# Croduino_Nova.net
KiCad netlist of a schematic drawn in EAGLE
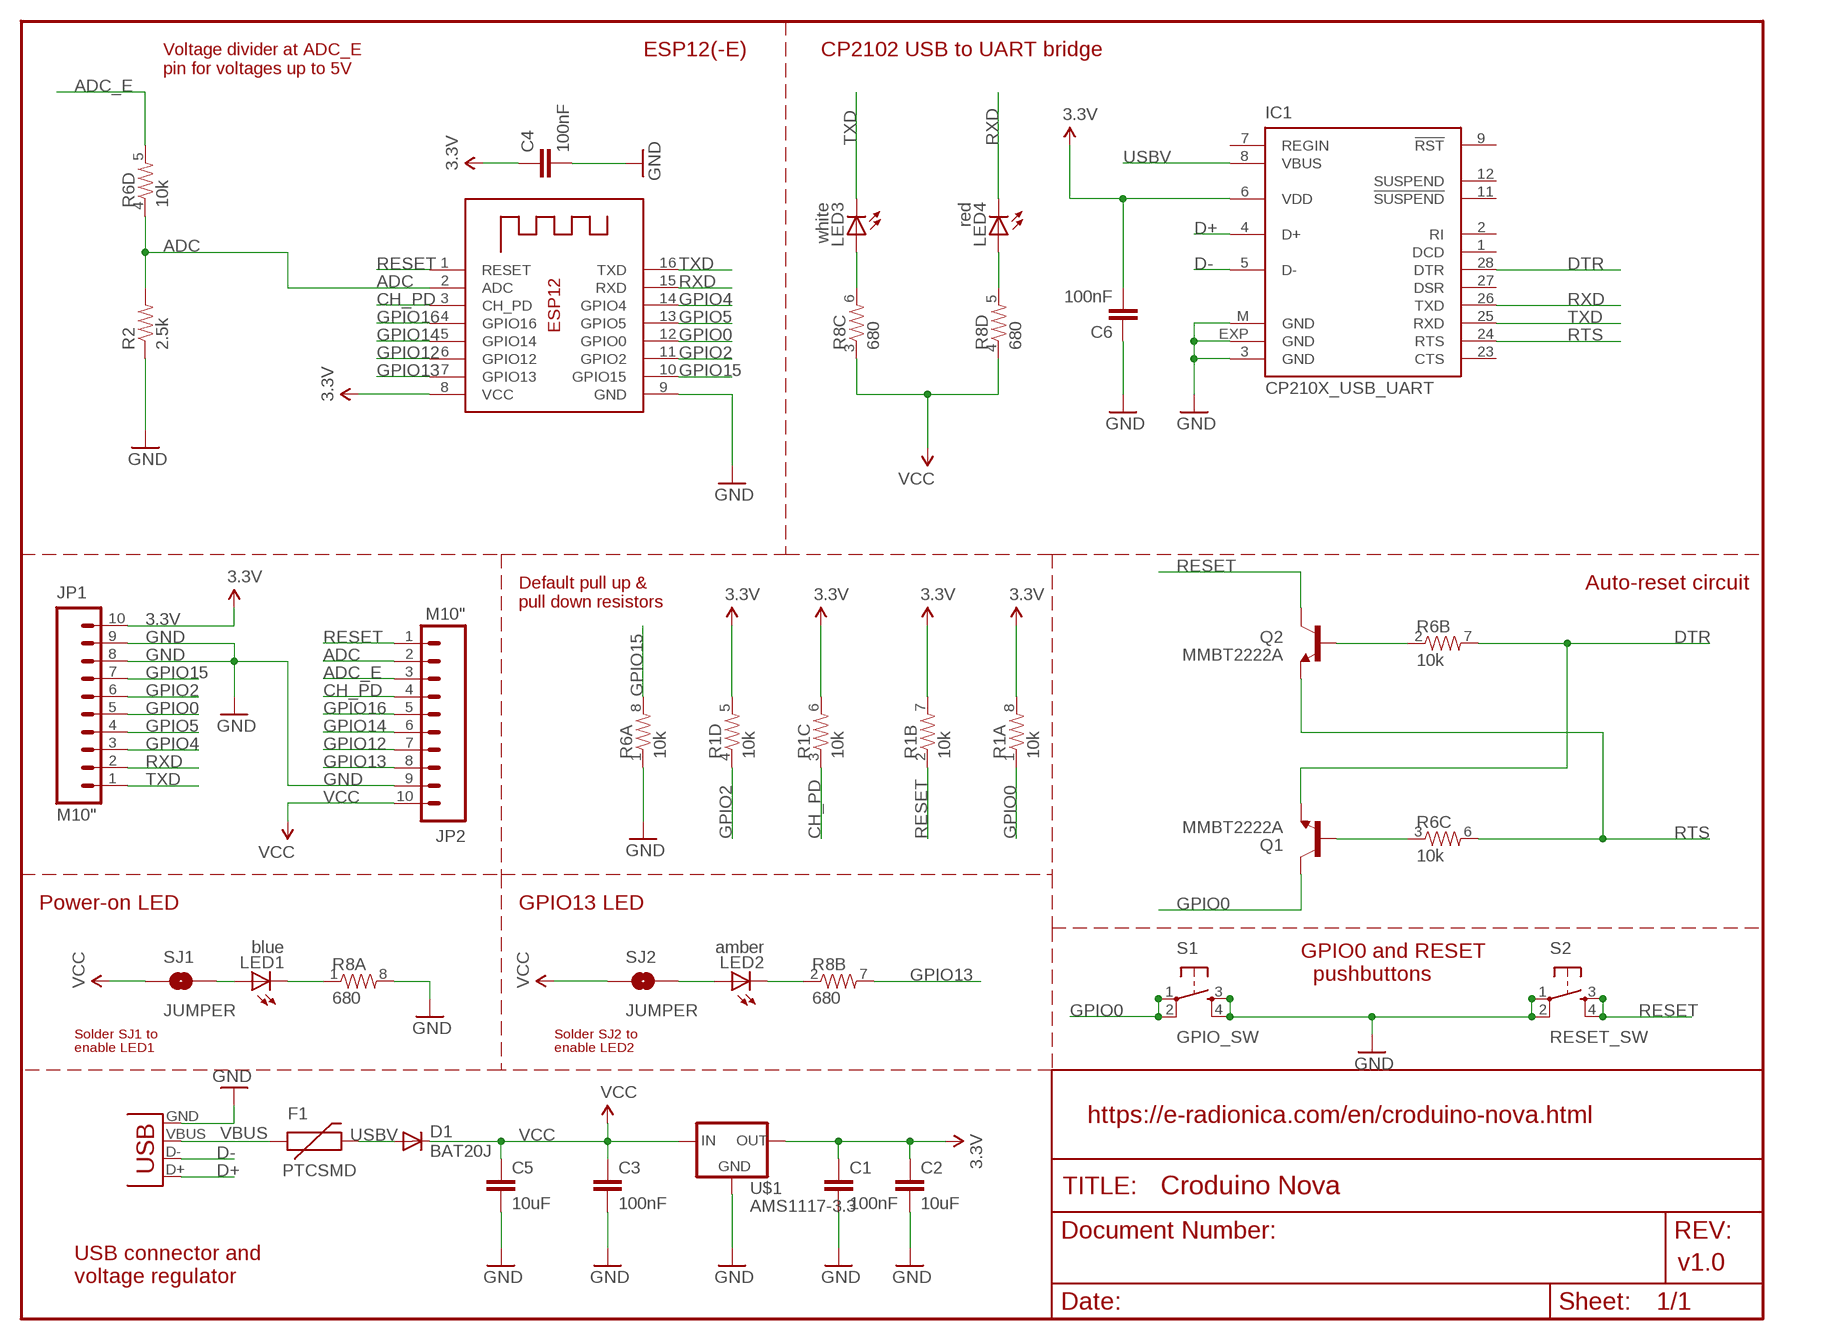
[diagram p0: schematic, sheet 1]

(export (version "E")
  (design (tool "Eeschema 10.0.6"))
  (components
    (comp (ref "C1")
      (value "100nF")
      (footprint "eagle-import:0603-CAP")
      (libsource (lib "eagle-import") (part "CAP0603-CAP"))
    )
    (comp (ref "C2")
      (value "10uF")
      (footprint "eagle-import:1206")
      (libsource (lib "eagle-import") (part "CAP1206"))
    )
    (comp (ref "C3")
      (value "100nF")
      (footprint "eagle-import:0603-CAP")
      (libsource (lib "eagle-import") (part "CAP0603-CAP"))
    )
    (comp (ref "C4")
      (value "100nF")
      (footprint "eagle-import:0603-CAP")
      (libsource (lib "eagle-import") (part "CAP0603-CAP"))
    )
    (comp (ref "C5")
      (value "10uF")
      (footprint "eagle-import:1206")
      (libsource (lib "eagle-import") (part "CAP1206"))
    )
    (comp (ref "C6")
      (value "100nF")
      (footprint "eagle-import:0603-CAP")
      (libsource (lib "eagle-import") (part "CAP0603-CAP"))
    )
    (comp (ref "D1")
      (value "BAT20J")
      (footprint "eagle-import:SOD-323")
      (libsource (lib "eagle-import") (part "DIODESOD"))
    )
    (comp (ref "F1")
      (value "PTCSMD")
      (footprint "eagle-import:PTC-1206")
      (libsource (lib "eagle-import") (part "PTCSMD"))
    )
    (comp (ref "IC1")
      (value "CP210X_USB_UART")
      (footprint "eagle-import:MLP28")
      (libsource (lib "eagle-import") (part "CP210X_USB_UART"))
    )
    (comp (ref "JP1")
      (value "M10\"")
      (footprint "eagle-import:1X10")
      (libsource (lib "eagle-import") (part "M10{dblquote}"))
    )
    (comp (ref "JP2")
      (value "M10\"")
      (footprint "eagle-import:1X10")
      (libsource (lib "eagle-import") (part "M10{dblquote}"))
    )
    (comp (ref "LED1")
      (value "blue")
      (footprint "eagle-import:CHIP-LED0805")
      (libsource (lib "eagle-import") (part "LEDCHIP-LED0805"))
    )
    (comp (ref "LED2")
      (value "amber")
      (footprint "eagle-import:CHIP-LED0805")
      (libsource (lib "eagle-import") (part "LEDCHIP-LED0805"))
    )
    (comp (ref "LED3")
      (value "white")
      (footprint "eagle-import:CHIP-LED0805")
      (libsource (lib "eagle-import") (part "LEDCHIP-LED0805"))
    )
    (comp (ref "LED4")
      (value "red")
      (footprint "eagle-import:CHIP-LED0805")
      (libsource (lib "eagle-import") (part "LEDCHIP-LED0805"))
    )
    (comp (ref "Q1")
      (value "MMBT2222A")
      (footprint "eagle-import:SOT23-3")
      (libsource (lib "eagle-import") (part "TRANSISTOR_NPNSOT23-3"))
    )
    (comp (ref "Q2")
      (value "MMBT2222A")
      (footprint "eagle-import:SOT23-3")
      (libsource (lib "eagle-import") (part "TRANSISTOR_NPNSOT23-3"))
    )
    (comp (ref "R1")
      (value "10k")
      (footprint "eagle-import:0603-ARV")
      (libsource (lib "eagle-import") (part "RESISTOR-ARRAY0603-ARV"))
    )
    (comp (ref "R2")
      (value "2.5k")
      (footprint "eagle-import:0603-RES")
      (libsource (lib "eagle-import") (part "RESISTOR0603-RES"))
    )
    (comp (ref "R6")
      (value "10k")
      (footprint "eagle-import:0603-ARV")
      (libsource (lib "eagle-import") (part "RESISTOR-ARRAY0603-ARV"))
    )
    (comp (ref "R8")
      (value "680")
      (footprint "eagle-import:0603-ARV")
      (libsource (lib "eagle-import") (part "RESISTOR-ARRAY0603-ARV"))
    )
    (comp (ref "S1")
      (value "GPIO_SW")
      (footprint "eagle-import:TACTILE_SWITCH_SMD")
      (libsource (lib "eagle-import") (part "TAC_SWITCHSMD"))
    )
    (comp (ref "S2")
      (value "RESET_SW")
      (footprint "eagle-import:TACTILE_SWITCH_SMD")
      (libsource (lib "eagle-import") (part "TAC_SWITCHSMD"))
    )
    (comp (ref "SJ1")
      (value "JUMPER")
      (footprint "eagle-import:SJ_2S")
      (libsource (lib "eagle-import") (part "SOLDERJUMPERNC"))
    )
    (comp (ref "SJ2")
      (value "JUMPER")
      (footprint "eagle-import:SJ_2S")
      (libsource (lib "eagle-import") (part "SOLDERJUMPERNC"))
    )
    (comp (ref "U$1")
      (value "AMS1117-3.3")
      (footprint "eagle-import:SOT223")
      (libsource (lib "eagle-import") (part "AMS1117-3.3"))
    )
    (comp (ref "X1")
      (value "ESP8266-12")
      (footprint "eagle-import:ESP-12")
      (libsource (lib "eagle-import") (part "ESP-12"))
    )
    (comp (ref "X2")
      (value "USB-MICROB")
      (footprint "eagle-import:USB-MICROB")
      (libsource (lib "eagle-import") (part "USB-MICROB"))
    )
  )
  (nets
    (net (code "1") (name "/ADC") (class "Default")
      (node (ref "JP2") (pin "2") (pinfunction "2_2") (pintype "passive"))
      (node (ref "R2") (pin "2") (pinfunction "2_2") (pintype "passive"))
      (node (ref "R6") (pin "4") (pinfunction "1_4") (pintype "passive"))
      (node (ref "X1") (pin "2") (pinfunction "ADC_2") (pintype "passive"))
    )
    (net (code "2") (name "/ADC_E") (class "Default")
      (node (ref "JP2") (pin "3") (pinfunction "3_3") (pintype "passive"))
      (node (ref "R6") (pin "5") (pinfunction "2_5") (pintype "passive"))
    )
    (net (code "3") (name "/CH_PD") (class "Default")
      (node (ref "JP2") (pin "4") (pinfunction "4_4") (pintype "passive"))
      (node (ref "R1") (pin "3") (pinfunction "1_3") (pintype "passive"))
      (node (ref "X1") (pin "3") (pinfunction "CH_PD_3") (pintype "input"))
    )
    (net (code "4") (name "/D+") (class "Default")
      (node (ref "IC1") (pin "4") (pinfunction "D+_4") (pintype "bidirectional"))
      (node (ref "X2") (pin "D+") (pinfunction "D+_D+") (pintype "bidirectional"))
    )
    (net (code "5") (name "/D-") (class "Default")
      (node (ref "IC1") (pin "5") (pinfunction "D-_5") (pintype "bidirectional"))
      (node (ref "X2") (pin "D-") (pinfunction "D-_D-") (pintype "bidirectional"))
    )
    (net (code "6") (name "/DTR") (class "Default")
      (node (ref "IC1") (pin "28") (pinfunction "DTR_28") (pintype "output"))
      (node (ref "Q1") (pin "2") (pinfunction "E_2") (pintype "passive"))
      (node (ref "R6") (pin "7") (pinfunction "2_7") (pintype "passive"))
    )
    (net (code "7") (name "/GPIO0") (class "Default")
      (node (ref "JP1") (pin "5") (pinfunction "5_5") (pintype "passive"))
      (node (ref "Q1") (pin "3") (pinfunction "C_3") (pintype "passive"))
      (node (ref "R1") (pin "1") (pinfunction "1_1") (pintype "passive"))
      (node (ref "S1") (pin "1") (pinfunction "1_1") (pintype "passive"))
      (node (ref "S1") (pin "2") (pinfunction "2_2") (pintype "passive"))
      (node (ref "X1") (pin "12") (pinfunction "GPIO0_12") (pintype "bidirectional"))
    )
    (net (code "8") (name "/GPIO2") (class "Default")
      (node (ref "JP1") (pin "6") (pinfunction "6_6") (pintype "passive"))
      (node (ref "R1") (pin "4") (pinfunction "1_4") (pintype "passive"))
      (node (ref "X1") (pin "11") (pinfunction "GPIO2_11") (pintype "bidirectional"))
    )
    (net (code "9") (name "/GPIO4") (class "Default")
      (node (ref "JP1") (pin "3") (pinfunction "3_3") (pintype "passive"))
      (node (ref "X1") (pin "14") (pinfunction "GPIO4_14") (pintype "bidirectional"))
    )
    (net (code "10") (name "/GPIO5") (class "Default")
      (node (ref "JP1") (pin "4") (pinfunction "4_4") (pintype "passive"))
      (node (ref "X1") (pin "13") (pinfunction "GPIO5_13") (pintype "bidirectional"))
    )
    (net (code "11") (name "/GPIO12") (class "Default")
      (node (ref "JP2") (pin "7") (pinfunction "7_7") (pintype "passive"))
      (node (ref "X1") (pin "6") (pinfunction "GPIO12_6") (pintype "bidirectional"))
    )
    (net (code "12") (name "/GPIO13") (class "Default")
      (node (ref "JP2") (pin "8") (pinfunction "8_8") (pintype "passive"))
      (node (ref "R8") (pin "7") (pinfunction "2_7") (pintype "passive"))
      (node (ref "X1") (pin "7") (pinfunction "GPIO13_7") (pintype "bidirectional"))
    )
    (net (code "13") (name "/GPIO14") (class "Default")
      (node (ref "JP2") (pin "6") (pinfunction "6_6") (pintype "passive"))
      (node (ref "X1") (pin "5") (pinfunction "GPIO14_5") (pintype "bidirectional"))
    )
    (net (code "14") (name "/GPIO15") (class "Default")
      (node (ref "JP1") (pin "7") (pinfunction "7_7") (pintype "passive"))
      (node (ref "R6") (pin "8") (pinfunction "2_8") (pintype "passive"))
      (node (ref "X1") (pin "10") (pinfunction "GPIO15_10") (pintype "bidirectional"))
    )
    (net (code "15") (name "/GPIO16") (class "Default")
      (node (ref "JP2") (pin "5") (pinfunction "5_5") (pintype "passive"))
      (node (ref "X1") (pin "4") (pinfunction "GPIO16_4") (pintype "bidirectional"))
    )
    (net (code "16") (name "/RESET") (class "Default")
      (node (ref "JP2") (pin "1") (pinfunction "1_1") (pintype "passive"))
      (node (ref "Q2") (pin "3") (pinfunction "C_3") (pintype "passive"))
      (node (ref "R1") (pin "2") (pinfunction "1_2") (pintype "passive"))
      (node (ref "S2") (pin "3") (pinfunction "3_3") (pintype "passive"))
      (node (ref "S2") (pin "4") (pinfunction "4_4") (pintype "passive"))
      (node (ref "X1") (pin "1") (pinfunction "RESET_1") (pintype "input"))
    )
    (net (code "17") (name "/RTS") (class "Default")
      (node (ref "IC1") (pin "24") (pinfunction "RTS_24") (pintype "output"))
      (node (ref "Q2") (pin "2") (pinfunction "E_2") (pintype "passive"))
      (node (ref "R6") (pin "6") (pinfunction "2_6") (pintype "passive"))
    )
    (net (code "18") (name "/RXD") (class "Default")
      (node (ref "IC1") (pin "26") (pinfunction "TXD_26") (pintype "output"))
      (node (ref "JP1") (pin "2") (pinfunction "2_2") (pintype "passive"))
      (node (ref "LED4") (pin "C") (pinfunction "C_C") (pintype "passive"))
      (node (ref "X1") (pin "15") (pinfunction "RXD_15") (pintype "input"))
    )
    (net (code "19") (name "/TXD") (class "Default")
      (node (ref "IC1") (pin "25") (pinfunction "RXD_25") (pintype "input"))
      (node (ref "JP1") (pin "1") (pinfunction "1_1") (pintype "passive"))
      (node (ref "LED3") (pin "C") (pinfunction "C_C") (pintype "passive"))
      (node (ref "X1") (pin "16") (pinfunction "TXD_16") (pintype "output"))
    )
    (net (code "20") (name "/USBV") (class "Default")
      (node (ref "D1") (pin "2") (pinfunction "A_2") (pintype "passive"))
      (node (ref "F1") (pin "2") (pinfunction "2_2") (pintype "bidirectional"))
      (node (ref "IC1") (pin "8") (pinfunction "VBUS_8") (pintype "input"))
    )
    (net (code "21") (name "/VBUS") (class "Default")
      (node (ref "F1") (pin "1") (pinfunction "1_1") (pintype "bidirectional"))
      (node (ref "X2") (pin "VBUS") (pinfunction "VBUS_VBUS") (pintype "bidirectional"))
    )
    (net (code "22") (name "3.3V") (class "Default")
      (node (ref "C1") (pin "1") (pinfunction "1_1") (pintype "passive"))
      (node (ref "C2") (pin "1") (pinfunction "1_1") (pintype "passive"))
      (node (ref "C4") (pin "1") (pinfunction "1_1") (pintype "passive"))
      (node (ref "C6") (pin "2") (pinfunction "2_2") (pintype "passive"))
      (node (ref "IC1") (pin "6") (pinfunction "VDD_6") (pintype "power_in"))
      (node (ref "JP1") (pin "10") (pinfunction "10_10") (pintype "passive"))
      (node (ref "R1") (pin "5") (pinfunction "2_5") (pintype "passive"))
      (node (ref "R1") (pin "6") (pinfunction "2_6") (pintype "passive"))
      (node (ref "R1") (pin "7") (pinfunction "2_7") (pintype "passive"))
      (node (ref "R1") (pin "8") (pinfunction "2_8") (pintype "passive"))
      (node (ref "U$1") (pin "4") (pinfunction "OUT_4") (pintype "output"))
      (node (ref "X1") (pin "8") (pinfunction "VCC_8") (pintype "power_in"))
    )
    (net (code "23") (name "GND") (class "Default")
      (node (ref "C1") (pin "2") (pinfunction "2_2") (pintype "passive"))
      (node (ref "C2") (pin "2") (pinfunction "2_2") (pintype "passive"))
      (node (ref "C3") (pin "2") (pinfunction "2_2") (pintype "passive"))
      (node (ref "C4") (pin "2") (pinfunction "2_2") (pintype "passive"))
      (node (ref "C5") (pin "2") (pinfunction "2_2") (pintype "passive"))
      (node (ref "C6") (pin "1") (pinfunction "1_1") (pintype "passive"))
      (node (ref "IC1") (pin "3") (pinfunction "GND_3") (pintype "power_in"))
      (node (ref "IC1") (pin "EXP") (pinfunction "GND_EXP") (pintype "power_in"))
      (node (ref "IC1") (pin "M") (pinfunction "GND_M") (pintype "power_in"))
      (node (ref "JP1") (pin "8") (pinfunction "8_8") (pintype "passive"))
      (node (ref "JP1") (pin "9") (pinfunction "9_9") (pintype "passive"))
      (node (ref "JP2") (pin "9") (pinfunction "9_9") (pintype "passive"))
      (node (ref "R2") (pin "1") (pinfunction "1_1") (pintype "passive"))
      (node (ref "R6") (pin "1") (pinfunction "1_1") (pintype "passive"))
      (node (ref "R8") (pin "8") (pinfunction "2_8") (pintype "passive"))
      (node (ref "S1") (pin "3") (pinfunction "3_3") (pintype "passive"))
      (node (ref "S1") (pin "4") (pinfunction "4_4") (pintype "passive"))
      (node (ref "S2") (pin "1") (pinfunction "1_1") (pintype "passive"))
      (node (ref "S2") (pin "2") (pinfunction "2_2") (pintype "passive"))
      (node (ref "U$1") (pin "1") (pinfunction "ADJ_1") (pintype "input"))
      (node (ref "X1") (pin "9") (pinfunction "GND_9") (pintype "power_in"))
      (node (ref "X2") (pin "GND") (pinfunction "GND_GND") (pintype "bidirectional"))
    )
    (net (code "24") (name "Net-(LED1-PadA)") (class "Default")
      (node (ref "LED1") (pin "A") (pinfunction "A_A") (pintype "passive"))
      (node (ref "SJ1") (pin "2") (pinfunction "2_2") (pintype "passive"))
    )
    (net (code "25") (name "Net-(LED1-PadC)") (class "Default")
      (node (ref "LED1") (pin "C") (pinfunction "C_C") (pintype "passive"))
      (node (ref "R8") (pin "1") (pinfunction "1_1") (pintype "passive"))
    )
    (net (code "26") (name "Net-(LED2-PadA)") (class "Default")
      (node (ref "LED2") (pin "A") (pinfunction "A_A") (pintype "passive"))
      (node (ref "SJ2") (pin "2") (pinfunction "2_2") (pintype "passive"))
    )
    (net (code "27") (name "Net-(Q1-B)") (class "Default")
      (node (ref "Q1") (pin "1") (pinfunction "B_1") (pintype "passive"))
      (node (ref "R6") (pin "3") (pinfunction "1_3") (pintype "passive"))
    )
    (net (code "28") (name "Net-(Q2-B)") (class "Default")
      (node (ref "Q2") (pin "1") (pinfunction "B_1") (pintype "passive"))
      (node (ref "R6") (pin "2") (pinfunction "1_2") (pintype "passive"))
    )
    (net (code "29") (name "Net-(R8B-1)") (class "Default")
      (node (ref "LED2") (pin "C") (pinfunction "C_C") (pintype "passive"))
      (node (ref "R8") (pin "2") (pinfunction "1_2") (pintype "passive"))
    )
    (net (code "30") (name "Net-(R8C-2)") (class "Default")
      (node (ref "LED3") (pin "A") (pinfunction "A_A") (pintype "passive"))
      (node (ref "R8") (pin "6") (pinfunction "2_6") (pintype "passive"))
    )
    (net (code "31") (name "Net-(R8D-2)") (class "Default")
      (node (ref "LED4") (pin "A") (pinfunction "A_A") (pintype "passive"))
      (node (ref "R8") (pin "5") (pinfunction "2_5") (pintype "passive"))
    )
    (net (code "32") (name "VCC") (class "Default")
      (node (ref "C3") (pin "1") (pinfunction "1_1") (pintype "passive"))
      (node (ref "C5") (pin "1") (pinfunction "1_1") (pintype "passive"))
      (node (ref "D1") (pin "1") (pinfunction "C_1") (pintype "passive"))
      (node (ref "JP2") (pin "10") (pinfunction "10_10") (pintype "passive"))
      (node (ref "R8") (pin "3") (pinfunction "1_3") (pintype "passive"))
      (node (ref "R8") (pin "4") (pinfunction "1_4") (pintype "passive"))
      (node (ref "SJ1") (pin "1") (pinfunction "1_1") (pintype "passive"))
      (node (ref "SJ2") (pin "1") (pinfunction "1_1") (pintype "passive"))
      (node (ref "U$1") (pin "3") (pinfunction "IN_3") (pintype "input"))
    )
    (net (code "33") (name "unconnected-(IC1-CTS-Pad23)") (class "Default")
      (node (ref "IC1") (pin "23") (pinfunction "CTS_23") (pintype "input"))
    )
    (net (code "34") (name "unconnected-(IC1-DCD-Pad1)") (class "Default")
      (node (ref "IC1") (pin "1") (pinfunction "DCD_1") (pintype "input"))
    )
    (net (code "35") (name "unconnected-(IC1-DSR-Pad27)") (class "Default")
      (node (ref "IC1") (pin "27") (pinfunction "DSR_27") (pintype "input"))
    )
    (net (code "36") (name "unconnected-(IC1-REGIN-Pad7)") (class "Default")
      (node (ref "IC1") (pin "7") (pinfunction "REGIN_7") (pintype "passive"))
    )
    (net (code "37") (name "unconnected-(IC1-RI-Pad2)") (class "Default")
      (node (ref "IC1") (pin "2") (pinfunction "RI_2") (pintype "input"))
    )
    (net (code "38") (name "unconnected-(IC1-SUSPEND-Pad12)") (class "Default")
      (node (ref "IC1") (pin "12") (pinfunction "SUSPEND_12") (pintype "output"))
    )
    (net (code "39") (name "unconnected-(IC1-~{RST}-Pad9)") (class "Default")
      (node (ref "IC1") (pin "9") (pinfunction "~{RST}_9") (pintype "bidirectional"))
    )
    (net (code "40") (name "unconnected-(IC1-~{SUSPEND}-Pad11)") (class "Default")
      (node (ref "IC1") (pin "11") (pinfunction "~{SUSPEND}_11") (pintype "output"))
    )
  )
)
